# Pulsar_Buddy_SM.net
KiCad netlist of a schematic drawn in EAGLE
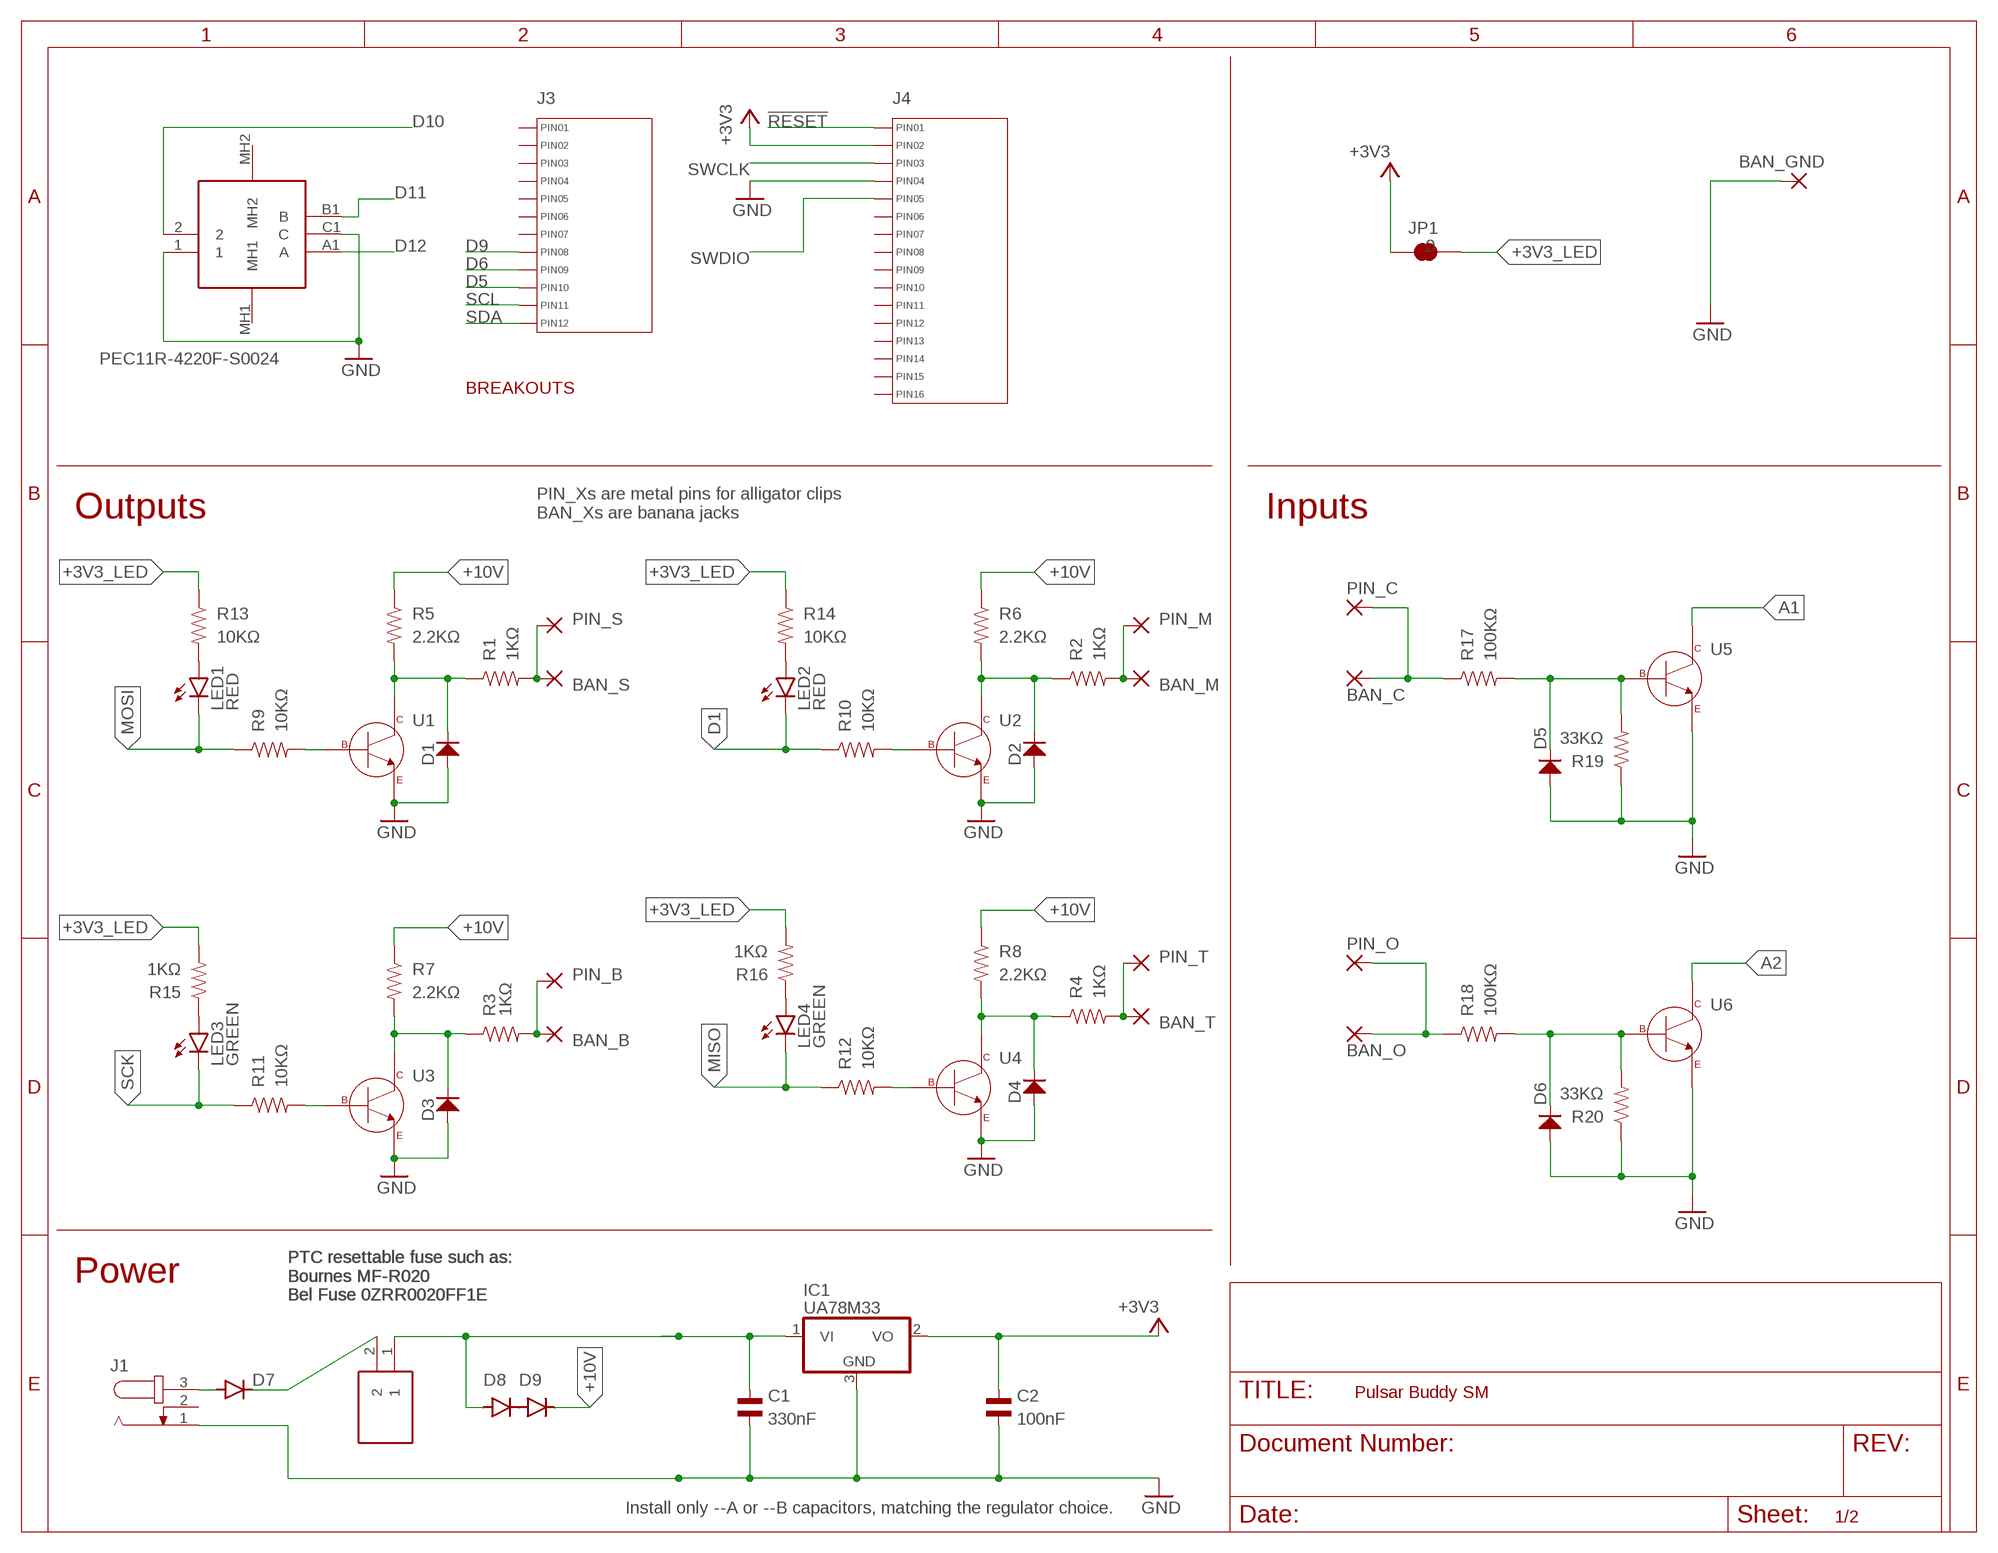
[diagram p0: schematic, sheet 1]
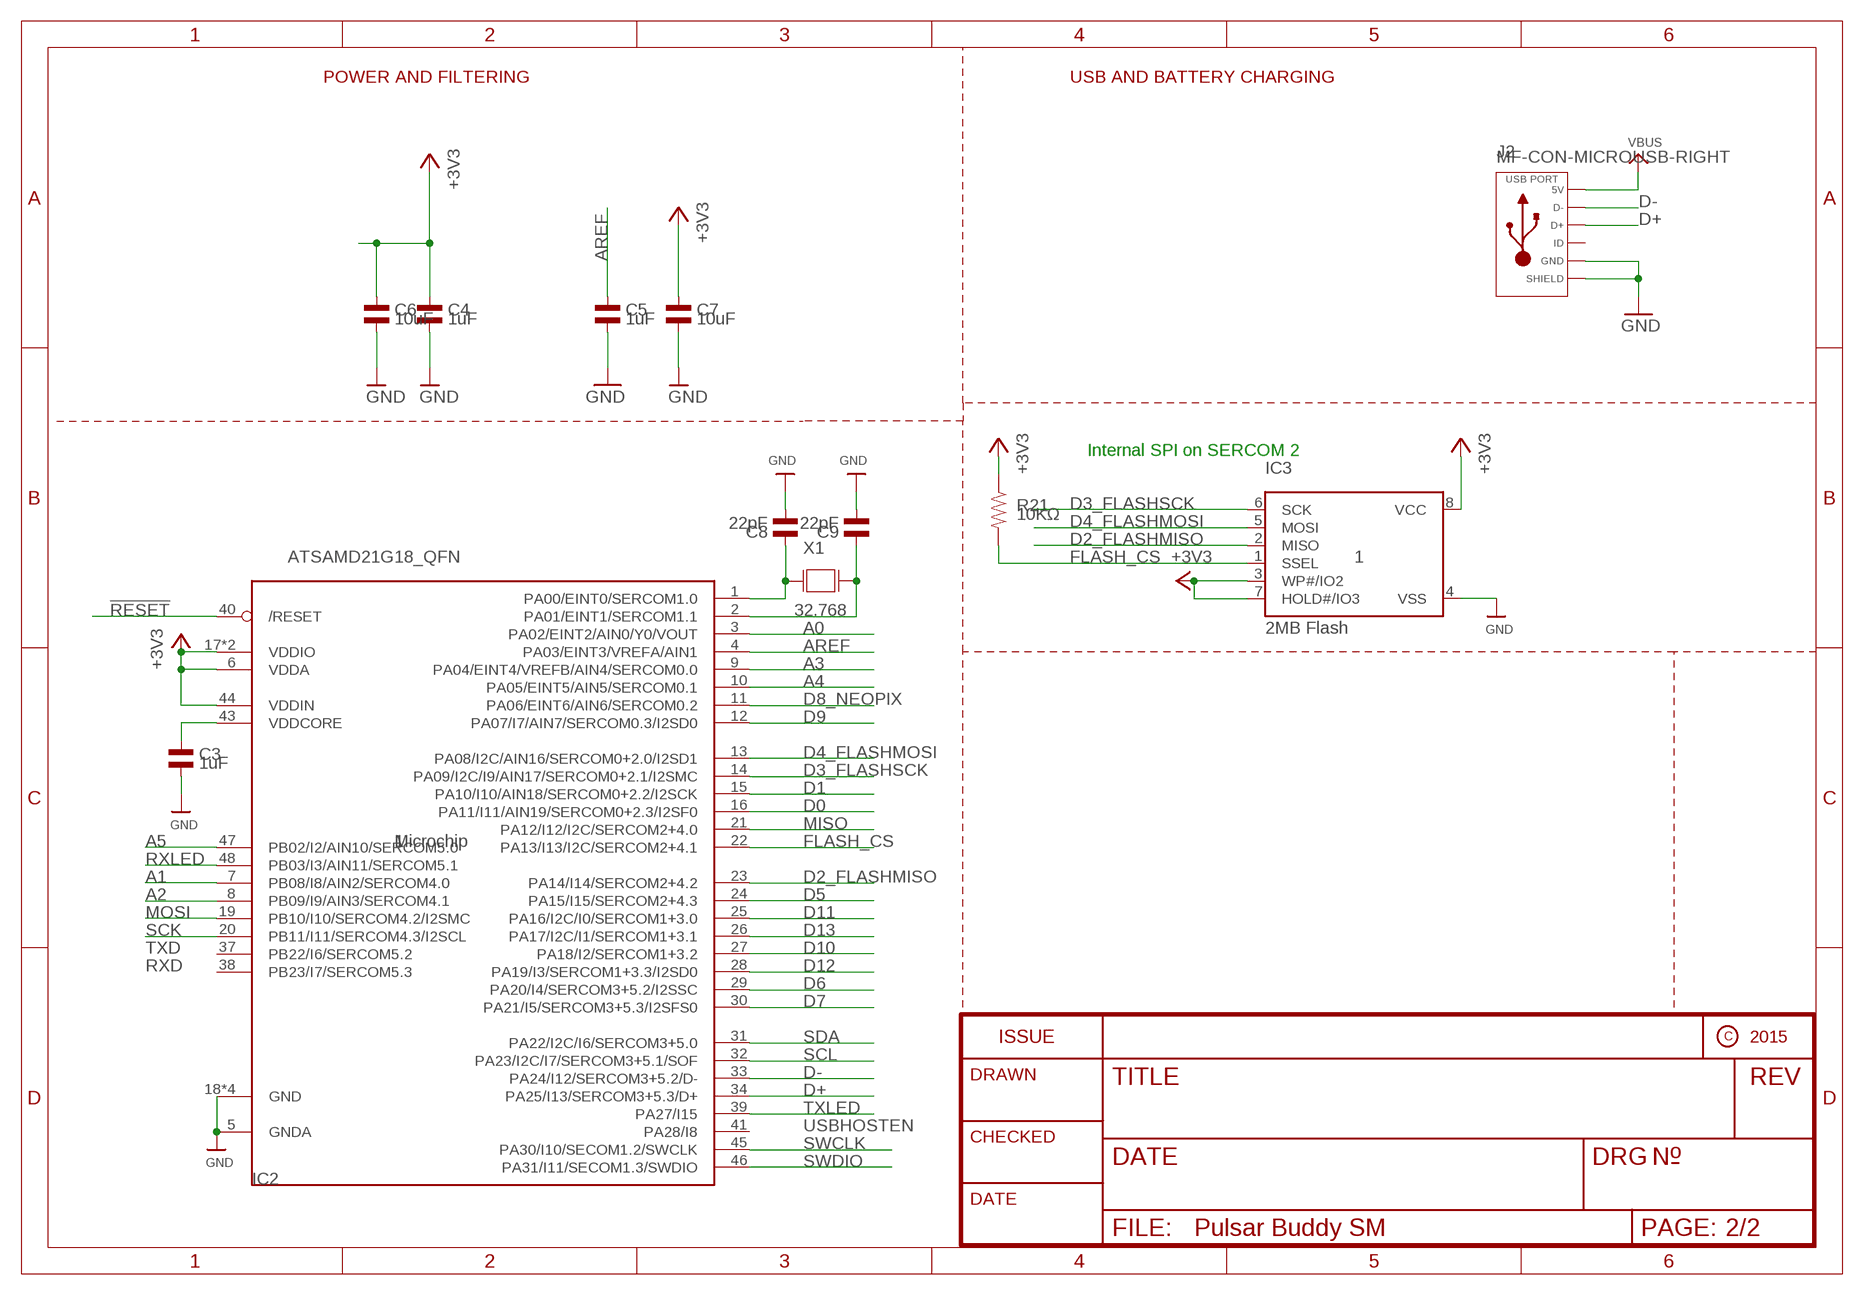
[diagram p1: schematic, sheet 2]

(export (version "E")
  (design (tool "Eeschema 10.0.6"))
  (components
    (comp (ref "C3")
      (value "1uF")
      (footprint "eagle-import:C0603")
      (fields (field (name "HOUSEPART") "YES") (field (name "MPN") "MF-CAP-0603-1uF"))
      (libsource (lib "eagle-import") (part "CAPACITOR_NP_0603"))
    )
    (comp (ref "C4")
      (value "1uF")
      (footprint "eagle-import:C0603")
      (fields (field (name "HOUSEPART") "YES") (field (name "MPN") "MF-CAP-0603-1uF"))
      (libsource (lib "eagle-import") (part "CAPACITOR_NP_0603"))
    )
    (comp (ref "C5")
      (value "1uF")
      (footprint "eagle-import:C0603")
      (fields (field (name "HOUSEPART") "YES") (field (name "MPN") "MF-CAP-0603-1uF"))
      (libsource (lib "eagle-import") (part "CAPACITOR_NP_0603"))
    )
    (comp (ref "C6")
      (value "10uF")
      (footprint "eagle-import:C0603")
      (fields (field (name "MFR") "AVX") (field (name "MPN") "0603ZD106KAT2A"))
      (libsource (lib "eagle-import") (part "CAPACITOR_NP_0603"))
    )
    (comp (ref "C7")
      (value "10uF")
      (footprint "eagle-import:C0603")
      (fields (field (name "MFR") "AVX") (field (name "MPN") "0603ZD106KAT2A"))
      (libsource (lib "eagle-import") (part "CAPACITOR_NP_0603"))
    )
    (comp (ref "C8")
      (value "22pF")
      (footprint "eagle-import:C0603")
      (fields (field (name "HOUSEPART") "YES") (field (name "MPN") "MF-CAP-0603-22pF"))
      (libsource (lib "eagle-import") (part "CAPACITOR_NP_0603"))
    )
    (comp (ref "C9")
      (value "22pF")
      (footprint "eagle-import:C0603")
      (fields (field (name "HOUSEPART") "YES") (field (name "MPN") "MF-CAP-0603-22pF"))
      (libsource (lib "eagle-import") (part "CAPACITOR_NP_0603"))
    )
    (comp (ref "IC2")
      (value "ATSAMD21G18_QFN")
      (footprint "eagle-import:TQFN48_7MM")
      (fields
        (field (name "MFR") "Microchip")
        (field (name "MPN") "SAMD21G18A-MU")
        (field (name "POPULATE") "1")
      )
      (libsource (lib "eagle-import") (part "ATSAMD21G_QFN"))
    )
    (comp (ref "IC3")
      (value "2MB Flash")
      (footprint "eagle-import:SOIC8_208MIL")
      (fields
        (field (name "MFR") "Cypress")
        (field (name "MPN") "S25FL064LABMFI010")
        (field (name "POPULATE") "1")
      )
      (libsource (lib "eagle-import") (part "SPIFLASH_SOIC8208MIL"))
    )
    (comp (ref "J2")
      (value "MF-CON-MICROUSB-RIGHT")
      (footprint "eagle-import:MICROUSB-RIGHT")
      (fields (field (name "HOUSEPART") "YES"))
      (libsource (lib "eagle-import") (part "USB_MICRO_RIGHT"))
    )
    (comp (ref "R21")
      (value "10KΩ")
      (footprint "eagle-import:R0603")
      (fields (field (name "MPN") "MF-RES-0603-10K"))
      (libsource (lib "eagle-import") (part "RESISTOR_0603"))
    )
    (comp (ref "U$34")
      (value "FIDUCIAL_100MIL")
      (footprint "eagle-import:FIDUCIAL_100MIL")
      (fields (field (name "HOUSEPART") "NO"))
      (libsource (lib "eagle-import") (part "FIDUCIAL_100MIL"))
    )
    (comp (ref "U$35")
      (value "FIDUCIAL_100MIL")
      (footprint "eagle-import:FIDUCIAL_100MIL")
      (fields (field (name "HOUSEPART") "NO"))
      (libsource (lib "eagle-import") (part "FIDUCIAL_100MIL"))
    )
    (comp (ref "X1")
      (value "32.768")
      (footprint "eagle-import:ECX-31B_SERIES")
      (fields
        (field (name "HOUSEPART") "NO")
        (field (name "MFR") "ECS International")
        (field (name "MPN") "ECS-.327-7-12-C-TR")
      )
      (libsource (lib "eagle-import") (part "CYRSTAL_ECX-31B"))
    )
    (comp (ref "BAN_B")
      (value "WIREPADBANANA")
      (footprint "eagle-import:BANANA")
      (fields (field (name "POPULATE") "0"))
      (libsource (lib "eagle-import") (part "WIREPADBANANA"))
    )
    (comp (ref "BAN_C")
      (value "WIREPADBANANA")
      (footprint "eagle-import:BANANA")
      (fields (field (name "POPULATE") "0"))
      (libsource (lib "eagle-import") (part "WIREPADBANANA"))
    )
    (comp (ref "BAN_GND")
      (value "WIREPADBANANA-GND")
      (footprint "eagle-import:BANANA-GND")
      (fields (field (name "POPULATE") "0"))
      (libsource (lib "eagle-import") (part "WIREPADBANANA-GND"))
    )
    (comp (ref "BAN_M")
      (value "WIREPADBANANA")
      (footprint "eagle-import:BANANA")
      (fields (field (name "POPULATE") "0"))
      (libsource (lib "eagle-import") (part "WIREPADBANANA"))
    )
    (comp (ref "BAN_O")
      (value "WIREPADBANANA")
      (footprint "eagle-import:BANANA")
      (fields (field (name "POPULATE") "0"))
      (libsource (lib "eagle-import") (part "WIREPADBANANA"))
    )
    (comp (ref "BAN_S")
      (value "WIREPADBANANA")
      (footprint "eagle-import:BANANA")
      (fields (field (name "POPULATE") "0"))
      (libsource (lib "eagle-import") (part "WIREPADBANANA"))
    )
    (comp (ref "BAN_T")
      (value "WIREPADBANANA")
      (footprint "eagle-import:BANANA")
      (fields (field (name "POPULATE") "0"))
      (libsource (lib "eagle-import") (part "WIREPADBANANA"))
    )
    (comp (ref "C1")
      (value "330nF")
      (footprint "eagle-import:C0603")
      (fields (field (name "MFR") "Yageo") (field (name "MPN") "CC0603ZRY5V7BB334"))
      (libsource (lib "eagle-import") (part "CAPACITOR_NP_0603"))
    )
    (comp (ref "C2")
      (value "100nF")
      (footprint "eagle-import:C0603")
      (fields (field (name "MFR") "Yageo") (field (name "MPN") "CC0603KRX7R9BB104"))
      (libsource (lib "eagle-import") (part "CAPACITOR_NP_0603"))
    )
    (comp (ref "D1")
      (value "MF-DIO-SOD123-BAT42")
      (footprint "eagle-import:SOD-123")
      (fields (field (name "HOUSEPART") "YES"))
      (libsource (lib "eagle-import") (part "DIODES_SOD-123_BAT42"))
    )
    (comp (ref "D2")
      (value "MF-DIO-SOD123-BAT42")
      (footprint "eagle-import:SOD-123")
      (fields (field (name "HOUSEPART") "YES"))
      (libsource (lib "eagle-import") (part "DIODES_SOD-123_BAT42"))
    )
    (comp (ref "D3")
      (value "MF-DIO-SOD123-BAT42")
      (footprint "eagle-import:SOD-123")
      (fields (field (name "HOUSEPART") "YES"))
      (libsource (lib "eagle-import") (part "DIODES_SOD-123_BAT42"))
    )
    (comp (ref "D4")
      (value "MF-DIO-SOD123-BAT42")
      (footprint "eagle-import:SOD-123")
      (fields (field (name "HOUSEPART") "YES"))
      (libsource (lib "eagle-import") (part "DIODES_SOD-123_BAT42"))
    )
    (comp (ref "D5")
      (value "MF-DIO-SOD123-BAT42")
      (footprint "eagle-import:SOD-123")
      (fields (field (name "HOUSEPART") "YES"))
      (libsource (lib "eagle-import") (part "DIODES_SOD-123_BAT42"))
    )
    (comp (ref "D6")
      (value "MF-DIO-SOD123-BAT42")
      (footprint "eagle-import:SOD-123")
      (fields (field (name "HOUSEPART") "YES"))
      (libsource (lib "eagle-import") (part "DIODES_SOD-123_BAT42"))
    )
    (comp (ref "D7")
      (value "CGRM4004-G")
      (footprint "eagle-import:SOD-123_MINI-SMA")
      (fields (field (name "MFR") "Comchip") (field (name "MPN") "CGRM4004-G") (field (name "POPULATE") "1"))
      (libsource (lib "eagle-import") (part "CGRM400-G4"))
    )
    (comp (ref "D8")
      (value "CGRM4004-G")
      (footprint "eagle-import:SOD-123_MINI-SMA")
      (fields (field (name "MFR") "Comchip") (field (name "MPN") "CGRM4004-G") (field (name "POPULATE") "1"))
      (libsource (lib "eagle-import") (part "CGRM400-G4"))
    )
    (comp (ref "D9")
      (value "CGRM4004-G")
      (footprint "eagle-import:SOD-123_MINI-SMA")
      (fields (field (name "MFR") "Comchip") (field (name "MPN") "CGRM4004-G") (field (name "POPULATE") "1"))
      (libsource (lib "eagle-import") (part "CGRM400-G4"))
    )
    (comp (ref "F1")
      (value "0ZCJ0020FF2E")
      (footprint "eagle-import:FUSC3216X75N")
      (fields (field (name "MFR") "Bel Fuse") (field (name "MPN") "0ZCJ0020FF2E"))
      (libsource (lib "eagle-import") (part "0ZCJ0020FF2E"))
    )
    (comp (ref "IC1")
      (value "UA78M33")
      (footprint "eagle-import:TO252")
      (fields
        (field (name "MFR") "Texas Instruments")
        (field (name "MPN") "UA78M33CKVURG3")
        (field (name "POPULATE") "1")
      )
      (libsource (lib "eagle-import") (part "78DT05"))
    )
    (comp (ref "J1")
      (value "JACK-PLUG0")
      (footprint "eagle-import:SPC4077")
      (fields (field (name "POPULATE") "0"))
      (libsource (lib "eagle-import") (part "JACK-PLUG0"))
    )
    (comp (ref "J3")
      (value "MF-CON-2.54mm-01x12")
      (footprint "eagle-import:PTH_2.54MM_01X12")
      (fields (field (name "HOUSEPART") "YES"))
      (libsource (lib "eagle-import") (part "CON_01X12_PTH_2.54MM"))
    )
    (comp (ref "J4")
      (value "MF-CON-2.54mm-01x16")
      (footprint "eagle-import:PTH_2.54MM_01X16")
      (fields (field (name "HOUSEPART") "YES"))
      (libsource (lib "eagle-import") (part "CON_01X16_PTH_2.54MM"))
    )
    (comp (ref "JP1")
      (value "JUMPER-SMT_2_NC_TRACE_SILK")
      (footprint "eagle-import:SMT-JUMPER_2_NC_TRACE_SILK")
      (fields (field (name "POPULATE") "0"))
      (libsource (lib "eagle-import") (part "JUMPER-SMT_2_NC_TRACE_SILK"))
    )
    (comp (ref "LED1")
      (value "RED")
      (footprint "eagle-import:LED5MM")
      (libsource (lib "eagle-import") (part "LED5MM"))
    )
    (comp (ref "LED2")
      (value "RED")
      (footprint "eagle-import:LED5MM")
      (libsource (lib "eagle-import") (part "LED5MM"))
    )
    (comp (ref "LED3")
      (value "GREEN")
      (footprint "eagle-import:LED5MM")
      (libsource (lib "eagle-import") (part "LED5MM"))
    )
    (comp (ref "LED4")
      (value "GREEN")
      (footprint "eagle-import:LED5MM")
      (libsource (lib "eagle-import") (part "LED5MM"))
    )
    (comp (ref "PIN_B")
      (value "WIREPAD")
      (footprint "eagle-import:M3")
      (fields (field (name "POPULATE") "0"))
      (libsource (lib "eagle-import") (part "WIREPAD"))
    )
    (comp (ref "PIN_C")
      (value "WIREPAD")
      (footprint "eagle-import:M3")
      (fields (field (name "POPULATE") "0"))
      (libsource (lib "eagle-import") (part "WIREPAD"))
    )
    (comp (ref "PIN_M")
      (value "WIREPAD")
      (footprint "eagle-import:M3")
      (fields (field (name "POPULATE") "0"))
      (libsource (lib "eagle-import") (part "WIREPAD"))
    )
    (comp (ref "PIN_O")
      (value "WIREPAD")
      (footprint "eagle-import:M3")
      (fields (field (name "POPULATE") "0"))
      (libsource (lib "eagle-import") (part "WIREPAD"))
    )
    (comp (ref "PIN_S")
      (value "WIREPAD")
      (footprint "eagle-import:M3")
      (fields (field (name "POPULATE") "0"))
      (libsource (lib "eagle-import") (part "WIREPAD"))
    )
    (comp (ref "PIN_T")
      (value "WIREPAD")
      (footprint "eagle-import:M3")
      (fields (field (name "POPULATE") "0"))
      (libsource (lib "eagle-import") (part "WIREPAD"))
    )
    (comp (ref "R1")
      (value "1KΩ")
      (footprint "eagle-import:R0603")
      (fields (field (name "MPN") "MF-RES-0603-1K"))
      (libsource (lib "eagle-import") (part "RESISTOR_0603"))
    )
    (comp (ref "R2")
      (value "1KΩ")
      (footprint "eagle-import:R0603")
      (fields (field (name "MPN") "MF-RES-0603-1K"))
      (libsource (lib "eagle-import") (part "RESISTOR_0603"))
    )
    (comp (ref "R3")
      (value "1KΩ")
      (footprint "eagle-import:R0603")
      (fields (field (name "MPN") "MF-RES-0603-1K"))
      (libsource (lib "eagle-import") (part "RESISTOR_0603"))
    )
    (comp (ref "R4")
      (value "1KΩ")
      (footprint "eagle-import:R0603")
      (fields (field (name "MPN") "MF-RES-0603-1K"))
      (libsource (lib "eagle-import") (part "RESISTOR_0603"))
    )
    (comp (ref "R5")
      (value "2.2KΩ")
      (footprint "eagle-import:R0603")
      (fields (field (name "MFR") "Yageo") (field (name "MPN") "RC0603JR-072K2L"))
      (libsource (lib "eagle-import") (part "RESISTOR_0603"))
    )
    (comp (ref "R6")
      (value "2.2KΩ")
      (footprint "eagle-import:R0603")
      (fields (field (name "MFR") "Yageo") (field (name "MPN") "RC0603JR-072K2L"))
      (libsource (lib "eagle-import") (part "RESISTOR_0603"))
    )
    (comp (ref "R7")
      (value "2.2KΩ")
      (footprint "eagle-import:R0603")
      (fields (field (name "MFR") "Yageo") (field (name "MPN") "RC0603JR-072K2L"))
      (libsource (lib "eagle-import") (part "RESISTOR_0603"))
    )
    (comp (ref "R8")
      (value "2.2KΩ")
      (footprint "eagle-import:R0603")
      (fields (field (name "MFR") "Yageo") (field (name "MPN") "RC0603JR-072K2L"))
      (libsource (lib "eagle-import") (part "RESISTOR_0603"))
    )
    (comp (ref "R9")
      (value "10KΩ")
      (footprint "eagle-import:R0603")
      (fields (field (name "MPN") "MF-RES-0603-10K"))
      (libsource (lib "eagle-import") (part "RESISTOR_0603"))
    )
    (comp (ref "R10")
      (value "10KΩ")
      (footprint "eagle-import:R0603")
      (fields (field (name "MPN") "MF-RES-0603-10K"))
      (libsource (lib "eagle-import") (part "RESISTOR_0603"))
    )
    (comp (ref "R11")
      (value "10KΩ")
      (footprint "eagle-import:R0603")
      (fields (field (name "MPN") "MF-RES-0603-10K"))
      (libsource (lib "eagle-import") (part "RESISTOR_0603"))
    )
    (comp (ref "R12")
      (value "10KΩ")
      (footprint "eagle-import:R0603")
      (fields (field (name "MPN") "MF-RES-0603-10K"))
      (libsource (lib "eagle-import") (part "RESISTOR_0603"))
    )
    (comp (ref "R13")
      (value "10KΩ")
      (footprint "eagle-import:R0603")
      (fields (field (name "MPN") "MF-RES-0603-10K"))
      (libsource (lib "eagle-import") (part "RESISTOR_0603"))
    )
    (comp (ref "R14")
      (value "10KΩ")
      (footprint "eagle-import:R0603")
      (fields (field (name "MPN") "MF-RES-0603-10K"))
      (libsource (lib "eagle-import") (part "RESISTOR_0603"))
    )
    (comp (ref "R15")
      (value "1KΩ")
      (footprint "eagle-import:R0603")
      (fields (field (name "MPN") "MF-RES-0603-1K"))
      (libsource (lib "eagle-import") (part "RESISTOR_0603"))
    )
    (comp (ref "R16")
      (value "1KΩ")
      (footprint "eagle-import:R0603")
      (fields (field (name "MPN") "MF-RES-0603-1K"))
      (libsource (lib "eagle-import") (part "RESISTOR_0603"))
    )
    (comp (ref "R17")
      (value "100KΩ")
      (footprint "eagle-import:R0603")
      (fields (field (name "MPN") "MF-RES-0603-100K"))
      (libsource (lib "eagle-import") (part "RESISTOR_0603"))
    )
    (comp (ref "R18")
      (value "100KΩ")
      (footprint "eagle-import:R0603")
      (fields (field (name "MPN") "MF-RES-0603-100K"))
      (libsource (lib "eagle-import") (part "RESISTOR_0603"))
    )
    (comp (ref "R19")
      (value "33KΩ")
      (footprint "eagle-import:R0603")
      (fields (field (name "MFR") "Yageo") (field (name "MPN") "RC0603FR-0733KL"))
      (libsource (lib "eagle-import") (part "RESISTOR_0603"))
    )
    (comp (ref "R20")
      (value "33KΩ")
      (footprint "eagle-import:R0603")
      (fields (field (name "MFR") "Yageo") (field (name "MPN") "RC0603FR-0733KL"))
      (libsource (lib "eagle-import") (part "RESISTOR_0603"))
    )
    (comp (ref "SW1")
      (value "PEC11R-4220F-S0024")
      (footprint "eagle-import:PEC11R4220FS0024")
      (fields
        (field (name "MOUSER_PART_NUMBER") "652-PEC11R-4220F-S24")
        (field (name "RS_PART_NUMBER") "7377767P")
        (field (name "MFR") "Bourns")
        (field (name "MPN") "PEC11R-4220F-S0024")
      )
      (libsource (lib "eagle-import") (part "PEC11R-4220F-S0024"))
    )
    (comp (ref "U1")
      (value "MF-DSC-SOT233-MMBT3904")
      (footprint "eagle-import:SOT-23-3")
      (fields (field (name "HOUSEPART") "YES"))
      (libsource (lib "eagle-import") (part "NPN_BJT_SOT-23-3MMBT3904"))
    )
    (comp (ref "U2")
      (value "MF-DSC-SOT233-MMBT3904")
      (footprint "eagle-import:SOT-23-3")
      (fields (field (name "HOUSEPART") "YES"))
      (libsource (lib "eagle-import") (part "NPN_BJT_SOT-23-3MMBT3904"))
    )
    (comp (ref "U3")
      (value "MF-DSC-SOT233-MMBT3904")
      (footprint "eagle-import:SOT-23-3")
      (fields (field (name "HOUSEPART") "YES"))
      (libsource (lib "eagle-import") (part "NPN_BJT_SOT-23-3MMBT3904"))
    )
    (comp (ref "U4")
      (value "MF-DSC-SOT233-MMBT3904")
      (footprint "eagle-import:SOT-23-3")
      (fields (field (name "HOUSEPART") "YES"))
      (libsource (lib "eagle-import") (part "NPN_BJT_SOT-23-3MMBT3904"))
    )
    (comp (ref "U5")
      (value "MF-DSC-SOT233-MMBT3904")
      (footprint "eagle-import:SOT-23-3")
      (fields (field (name "HOUSEPART") "YES"))
      (libsource (lib "eagle-import") (part "NPN_BJT_SOT-23-3MMBT3904"))
    )
    (comp (ref "U6")
      (value "MF-DSC-SOT233-MMBT3904")
      (footprint "eagle-import:SOT-23-3")
      (fields (field (name "HOUSEPART") "YES"))
      (libsource (lib "eagle-import") (part "NPN_BJT_SOT-23-3MMBT3904"))
    )
  )
  (nets
    (net (code "1") (name "+3V3") (class "Default")
      (node (ref "C2") (pin "P$1") (pinfunction "P$1_P$1") (pintype "passive"))
      (node (ref "C4") (pin "P$1") (pinfunction "P$1_P$1") (pintype "passive"))
      (node (ref "C6") (pin "P$1") (pinfunction "P$1_P$1") (pintype "passive"))
      (node (ref "C7") (pin "P$1") (pinfunction "P$1_P$1") (pintype "passive"))
      (node (ref "IC1") (pin "2") (pinfunction "VO_2") (pintype "passive"))
      (node (ref "IC2") (pin "17") (pinfunction "VDDIO_17") (pintype "power_in"))
      (node (ref "IC2") (pin "36") (pinfunction "VDDIO_36") (pintype "power_in"))
      (node (ref "IC2") (pin "44") (pinfunction "VDDIN_44") (pintype "power_in"))
      (node (ref "IC2") (pin "6") (pinfunction "VDDA_6") (pintype "power_in"))
      (node (ref "IC3") (pin "3") (pinfunction "WP#/IO2_3") (pintype "bidirectional"))
      (node (ref "IC3") (pin "7") (pinfunction "HOLD#/IO3_7") (pintype "bidirectional"))
      (node (ref "IC3") (pin "8") (pinfunction "VCC_8") (pintype "bidirectional"))
      (node (ref "J4") (pin "P$2") (pinfunction "PIN2_P$2") (pintype "bidirectional"))
      (node (ref "JP1") (pin "1") (pinfunction "1_1") (pintype "passive"))
      (node (ref "R21") (pin "P$1") (pinfunction "P$1_P$1") (pintype "passive"))
    )
    (net (code "2") (name "+3V3_LED") (class "Default")
      (node (ref "JP1") (pin "2") (pinfunction "2_2") (pintype "passive"))
      (node (ref "R13") (pin "P$1") (pinfunction "P$1_P$1") (pintype "passive"))
      (node (ref "R14") (pin "P$1") (pinfunction "P$1_P$1") (pintype "passive"))
      (node (ref "R15") (pin "P$2") (pinfunction "P$2_P$2") (pintype "passive"))
      (node (ref "R16") (pin "P$2") (pinfunction "P$2_P$2") (pintype "passive"))
    )
    (net (code "3") (name "+10V") (class "Default")
      (node (ref "D9") (pin "C") (pinfunction "C_C") (pintype "passive"))
      (node (ref "R5") (pin "P$1") (pinfunction "P$1_P$1") (pintype "passive"))
      (node (ref "R6") (pin "P$1") (pinfunction "P$1_P$1") (pintype "passive"))
      (node (ref "R7") (pin "P$1") (pinfunction "P$1_P$1") (pintype "passive"))
      (node (ref "R8") (pin "P$1") (pinfunction "P$1_P$1") (pintype "passive"))
    )
    (net (code "4") (name "A0") (class "Default")
      (node (ref "IC2") (pin "3") (pinfunction "PA02/EINT2/AIN0/Y0/VOUT_3") (pintype "bidirectional"))
    )
    (net (code "5") (name "A1") (class "Default")
      (node (ref "IC2") (pin "7") (pinfunction "PB08/I8/AIN2/SERCOM4.0_7") (pintype "bidirectional"))
      (node (ref "U5") (pin "P$3") (pinfunction "COLLECTOR_P$3") (pintype "bidirectional"))
    )
    (net (code "6") (name "A2") (class "Default")
      (node (ref "IC2") (pin "8") (pinfunction "PB09/I9/AIN3/SERCOM4.1_8") (pintype "bidirectional"))
      (node (ref "U6") (pin "P$3") (pinfunction "COLLECTOR_P$3") (pintype "bidirectional"))
    )
    (net (code "7") (name "A3") (class "Default")
      (node (ref "IC2") (pin "9") (pinfunction "PA04/EINT4/VREFB/AIN4/SERCOM0.0_9") (pintype "bidirectional"))
    )
    (net (code "8") (name "A4") (class "Default")
      (node (ref "IC2") (pin "10") (pinfunction "PA05/EINT5/AIN5/SERCOM0.1_10") (pintype "bidirectional"))
    )
    (net (code "9") (name "A5") (class "Default")
      (node (ref "IC2") (pin "47") (pinfunction "PB02/I2/AIN10/SERCOM5.0_47") (pintype "bidirectional"))
    )
    (net (code "10") (name "AREF") (class "Default")
      (node (ref "C5") (pin "P$1") (pinfunction "P$1_P$1") (pintype "passive"))
      (node (ref "IC2") (pin "4") (pinfunction "PA03/EINT3/VREFA/AIN1_4") (pintype "bidirectional"))
    )
    (net (code "11") (name "D+") (class "Default")
      (node (ref "IC2") (pin "34") (pinfunction "PA25/I13/SERCOM3+5.3/D+_34") (pintype "bidirectional"))
      (node (ref "J2") (pin "3") (pinfunction "D+_3") (pintype "bidirectional"))
    )
    (net (code "12") (name "D-") (class "Default")
      (node (ref "IC2") (pin "33") (pinfunction "PA24/I12/SERCOM3+5.2/D-_33") (pintype "bidirectional"))
      (node (ref "J2") (pin "2") (pinfunction "D-_2") (pintype "bidirectional"))
    )
    (net (code "13") (name "D0") (class "Default")
      (node (ref "IC2") (pin "16") (pinfunction "PA11/I11/AIN19/SERCOM0+2.3/I2SF0_16") (pintype "bidirectional"))
    )
    (net (code "14") (name "D1") (class "Default")
      (node (ref "IC2") (pin "15") (pinfunction "PA10/I10/AIN18/SERCOM0+2.2/I2SCK_15") (pintype "bidirectional"))
      (node (ref "LED2") (pin "K") (pinfunction "C_K") (pintype "passive"))
      (node (ref "R10") (pin "P$1") (pinfunction "P$1_P$1") (pintype "passive"))
    )
    (net (code "15") (name "D2_FLASHMISO") (class "Default")
      (node (ref "IC2") (pin "23") (pinfunction "PA14/I14/SERCOM2+4.2_23") (pintype "bidirectional"))
      (node (ref "IC3") (pin "2") (pinfunction "MISO_2") (pintype "bidirectional"))
    )
    (net (code "16") (name "D3_FLASHSCK") (class "Default")
      (node (ref "IC2") (pin "14") (pinfunction "PA09/I2C/I9/AIN17/SERCOM0+2.1/I2SMC_14") (pintype "bidirectional"))
      (node (ref "IC3") (pin "6") (pinfunction "SCK_6") (pintype "bidirectional"))
    )
    (net (code "17") (name "D4_FLASHMOSI") (class "Default")
      (node (ref "IC2") (pin "13") (pinfunction "PA08/I2C/AIN16/SERCOM0+2.0/I2SD1_13") (pintype "bidirectional"))
      (node (ref "IC3") (pin "5") (pinfunction "MOSI_5") (pintype "bidirectional"))
    )
    (net (code "18") (name "D5") (class "Default")
      (node (ref "IC2") (pin "24") (pinfunction "PA15/I15/SERCOM2+4.3_24") (pintype "bidirectional"))
      (node (ref "J3") (pin "P$10") (pinfunction "PIN10_P$10") (pintype "bidirectional"))
    )
    (net (code "19") (name "D6") (class "Default")
      (node (ref "IC2") (pin "29") (pinfunction "PA20/I4/SERCOM3+5.2/I2SSC_29") (pintype "bidirectional"))
      (node (ref "J3") (pin "P$9") (pinfunction "PIN9_P$9") (pintype "bidirectional"))
    )
    (net (code "20") (name "D7") (class "Default")
      (node (ref "IC2") (pin "30") (pinfunction "PA21/I5/SERCOM3+5.3/I2SFS0_30") (pintype "bidirectional"))
    )
    (net (code "21") (name "D8_NEOPIX") (class "Default")
      (node (ref "IC2") (pin "11") (pinfunction "PA06/EINT6/AIN6/SERCOM0.2_11") (pintype "bidirectional"))
    )
    (net (code "22") (name "D9") (class "Default")
      (node (ref "IC2") (pin "12") (pinfunction "PA07/I7/AIN7/SERCOM0.3/I2SD0_12") (pintype "bidirectional"))
      (node (ref "J3") (pin "P$8") (pinfunction "PIN8_P$8") (pintype "bidirectional"))
    )
    (net (code "23") (name "D10") (class "Default")
      (node (ref "IC2") (pin "27") (pinfunction "PA18/I2/SERCOM1+3.2_27") (pintype "bidirectional"))
      (node (ref "SW1") (pin "2") (pinfunction "2_2") (pintype "bidirectional"))
    )
    (net (code "24") (name "D11") (class "Default")
      (node (ref "IC2") (pin "25") (pinfunction "PA16/I2C/I0/SERCOM1+3.0_25") (pintype "bidirectional"))
      (node (ref "SW1") (pin "B1") (pinfunction "B_B1") (pintype "bidirectional"))
    )
    (net (code "25") (name "D12") (class "Default")
      (node (ref "IC2") (pin "28") (pinfunction "PA19/I3/SERCOM1+3.3/I2SD0_28") (pintype "bidirectional"))
      (node (ref "SW1") (pin "A1") (pinfunction "A_A1") (pintype "bidirectional"))
    )
    (net (code "26") (name "D13") (class "Default")
      (node (ref "IC2") (pin "26") (pinfunction "PA17/I2C/I1/SERCOM1+3.1_26") (pintype "bidirectional"))
    )
    (net (code "27") (name "FLASH_CS") (class "Default")
      (node (ref "IC2") (pin "22") (pinfunction "PA13/I13/I2C/SERCOM2+4.1_22") (pintype "bidirectional"))
      (node (ref "IC3") (pin "1") (pinfunction "SSEL_1") (pintype "bidirectional"))
      (node (ref "R21") (pin "P$2") (pinfunction "P$2_P$2") (pintype "passive"))
    )
    (net (code "28") (name "GND") (class "Default")
      (node (ref "BAN_GND") (pin "C") (pinfunction "P_C") (pintype "passive"))
      (node (ref "C1") (pin "P$2") (pinfunction "P$2_P$2") (pintype "passive"))
      (node (ref "C2") (pin "P$2") (pinfunction "P$2_P$2") (pintype "passive"))
      (node (ref "C3") (pin "P$2") (pinfunction "P$2_P$2") (pintype "passive"))
      (node (ref "C4") (pin "P$2") (pinfunction "P$2_P$2") (pintype "passive"))
      (node (ref "C5") (pin "P$2") (pinfunction "P$2_P$2") (pintype "passive"))
      (node (ref "C6") (pin "P$2") (pinfunction "P$2_P$2") (pintype "passive"))
      (node (ref "C7") (pin "P$2") (pinfunction "P$2_P$2") (pintype "passive"))
      (node (ref "C8") (pin "P$2") (pinfunction "P$2_P$2") (pintype "passive"))
      (node (ref "C9") (pin "P$2") (pinfunction "P$2_P$2") (pintype "passive"))
      (node (ref "D1") (pin "ANODE") (pinfunction "ANODE_ANODE") (pintype "bidirectional"))
      (node (ref "D2") (pin "ANODE") (pinfunction "ANODE_ANODE") (pintype "bidirectional"))
      (node (ref "D3") (pin "ANODE") (pinfunction "ANODE_ANODE") (pintype "bidirectional"))
      (node (ref "D4") (pin "ANODE") (pinfunction "ANODE_ANODE") (pintype "bidirectional"))
      (node (ref "D5") (pin "ANODE") (pinfunction "ANODE_ANODE") (pintype "bidirectional"))
      (node (ref "D6") (pin "ANODE") (pinfunction "ANODE_ANODE") (pintype "bidirectional"))
      (node (ref "IC1") (pin "3") (pinfunction "GND_3") (pintype "passive"))
      (node (ref "IC2") (pin "18") (pinfunction "GND_18") (pintype "power_in"))
      (node (ref "IC2") (pin "35") (pinfunction "GND_35") (pintype "power_in"))
      (node (ref "IC2") (pin "42") (pinfunction "GND_42") (pintype "power_in"))
      (node (ref "IC2") (pin "5") (pinfunction "GNDA_5") (pintype "power_in"))
      (node (ref "IC2") (pin "THERMAL") (pinfunction "GND_THERMAL") (pintype "power_in"))
      (node (ref "IC3") (pin "4") (pinfunction "VSS_4") (pintype "bidirectional"))
      (node (ref "J1") (pin "1") (pinfunction "1_1") (pintype "passive"))
      (node (ref "J2") (pin "5") (pinfunction "GND_5") (pintype "power_in"))
      (node (ref "J2") (pin "S1") (pinfunction "SLD_S1") (pintype "power_in"))
      (node (ref "J2") (pin "S2") (pinfunction "SLD_S2") (pintype "power_in"))
      (node (ref "J2") (pin "S3") (pinfunction "SLD_S3") (pintype "power_in"))
      (node (ref "J2") (pin "S4") (pinfunction "SLD_S4") (pintype "power_in"))
      (node (ref "J2") (pin "S5") (pinfunction "SLD_S5") (pintype "power_in"))
      (node (ref "J2") (pin "S6") (pinfunction "SLD_S6") (pintype "power_in"))
      (node (ref "J4") (pin "P$4") (pinfunction "PIN4_P$4") (pintype "bidirectional"))
      (node (ref "R19") (pin "P$1") (pinfunction "P$1_P$1") (pintype "passive"))
      (node (ref "R20") (pin "P$1") (pinfunction "P$1_P$1") (pintype "passive"))
      (node (ref "SW1") (pin "1") (pinfunction "1_1") (pintype "bidirectional"))
      (node (ref "SW1") (pin "C1") (pinfunction "C_C1") (pintype "bidirectional"))
      (node (ref "U1") (pin "P$2") (pinfunction "EMITTER_P$2") (pintype "bidirectional"))
      (node (ref "U2") (pin "P$2") (pinfunction "EMITTER_P$2") (pintype "bidirectional"))
      (node (ref "U3") (pin "P$2") (pinfunction "EMITTER_P$2") (pintype "bidirectional"))
      (node (ref "U4") (pin "P$2") (pinfunction "EMITTER_P$2") (pintype "bidirectional"))
      (node (ref "U5") (pin "P$2") (pinfunction "EMITTER_P$2") (pintype "bidirectional"))
      (node (ref "U6") (pin "P$2") (pinfunction "EMITTER_P$2") (pintype "bidirectional"))
    )
    (net (code "29") (name "MISO") (class "Default")
      (node (ref "IC2") (pin "21") (pinfunction "PA12/I12/I2C/SERCOM2+4.0_21") (pintype "bidirectional"))
      (node (ref "LED4") (pin "K") (pinfunction "C_K") (pintype "passive"))
      (node (ref "R12") (pin "P$1") (pinfunction "P$1_P$1") (pintype "passive"))
    )
    (net (code "30") (name "MOSI") (class "Default")
      (node (ref "IC2") (pin "19") (pinfunction "PB10/I10/SERCOM4.2/I2SMC_19") (pintype "bidirectional"))
      (node (ref "LED1") (pin "K") (pinfunction "C_K") (pintype "passive"))
      (node (ref "R9") (pin "P$1") (pinfunction "P$1_P$1") (pintype "passive"))
    )
    (net (code "31") (name "Net-(BAN_B-P)") (class "Default")
      (node (ref "BAN_B") (pin "C") (pinfunction "P_C") (pintype "passive"))
      (node (ref "PIN_B") (pin "1") (pinfunction "P_1") (pintype "passive"))
      (node (ref "R3") (pin "P$2") (pinfunction "P$2_P$2") (pintype "passive"))
    )
    (net (code "32") (name "Net-(BAN_C-P)") (class "Default")
      (node (ref "BAN_C") (pin "C") (pinfunction "P_C") (pintype "passive"))
      (node (ref "PIN_C") (pin "1") (pinfunction "P_1") (pintype "passive"))
      (node (ref "R17") (pin "P$1") (pinfunction "P$1_P$1") (pintype "passive"))
    )
    (net (code "33") (name "Net-(BAN_M-P)") (class "Default")
      (node (ref "BAN_M") (pin "C") (pinfunction "P_C") (pintype "passive"))
      (node (ref "PIN_M") (pin "1") (pinfunction "P_1") (pintype "passive"))
      (node (ref "R2") (pin "P$2") (pinfunction "P$2_P$2") (pintype "passive"))
    )
    (net (code "34") (name "Net-(BAN_O-P)") (class "Default")
      (node (ref "BAN_O") (pin "C") (pinfunction "P_C") (pintype "passive"))
      (node (ref "PIN_O") (pin "1") (pinfunction "P_1") (pintype "passive"))
      (node (ref "R18") (pin "P$1") (pinfunction "P$1_P$1") (pintype "passive"))
    )
    (net (code "35") (name "Net-(BAN_S-P)") (class "Default")
      (node (ref "BAN_S") (pin "C") (pinfunction "P_C") (pintype "passive"))
      (node (ref "PIN_S") (pin "1") (pinfunction "P_1") (pintype "passive"))
      (node (ref "R1") (pin "P$2") (pinfunction "P$2_P$2") (pintype "passive"))
    )
    (net (code "36") (name "Net-(BAN_T-P)") (class "Default")
      (node (ref "BAN_T") (pin "C") (pinfunction "P_C") (pintype "passive"))
      (node (ref "PIN_T") (pin "1") (pinfunction "P_1") (pintype "passive"))
      (node (ref "R4") (pin "P$2") (pinfunction "P$2_P$2") (pintype "passive"))
    )
    (net (code "37") (name "Net-(D7-PadA)") (class "Default")
      (node (ref "D7") (pin "A") (pinfunction "A_A") (pintype "passive"))
      (node (ref "J1") (pin "3") (pinfunction "3_3") (pintype "passive"))
    )
    (net (code "38") (name "Net-(D7-PadC)") (class "Default")
      (node (ref "D7") (pin "C") (pinfunction "C_C") (pintype "passive"))
      (node (ref "F1") (pin "2") (pinfunction "2_2") (pintype "bidirectional"))
    )
    (net (code "39") (name "Net-(D8-PadC)") (class "Default")
      (node (ref "D8") (pin "C") (pinfunction "C_C") (pintype "passive"))
      (node (ref "D9") (pin "A") (pinfunction "A_A") (pintype "passive"))
    )
    (net (code "40") (name "Net-(IC1-VI)") (class "Default")
      (node (ref "C1") (pin "P$1") (pinfunction "P$1_P$1") (pintype "passive"))
      (node (ref "D8") (pin "A") (pinfunction "A_A") (pintype "passive"))
      (node (ref "F1") (pin "1") (pinfunction "1_1") (pintype "bidirectional"))
      (node (ref "IC1") (pin "1") (pinfunction "VI_1") (pintype "input"))
    )
    (net (code "41") (name "Net-(IC2-PA00{slash}EINT0{slash}SERCOM1.0)") (class "Default")
      (node (ref "C8") (pin "P$1") (pinfunction "P$1_P$1") (pintype "passive"))
      (node (ref "IC2") (pin "1") (pinfunction "PA00/EINT0/SERCOM1.0_1") (pintype "bidirectional"))
      (node (ref "X1") (pin "P$1") (pinfunction "X0_P$1") (pintype "bidirectional"))
    )
    (net (code "42") (name "Net-(IC2-PA01{slash}EINT1{slash}SERCOM1.1)") (class "Default")
      (node (ref "C9") (pin "P$1") (pinfunction "P$1_P$1") (pintype "passive"))
      (node (ref "IC2") (pin "2") (pinfunction "PA01/EINT1/SERCOM1.1_2") (pintype "bidirectional"))
      (node (ref "X1") (pin "P$2") (pinfunction "X1_P$2") (pintype "bidirectional"))
    )
    (net (code "43") (name "Net-(IC2-VDDCORE)") (class "Default")
      (node (ref "C3") (pin "P$1") (pinfunction "P$1_P$1") (pintype "passive"))
      (node (ref "IC2") (pin "43") (pinfunction "VDDCORE_43") (pintype "power_in"))
    )
    (net (code "44") (name "Net-(LED1-PadA)") (class "Default")
      (node (ref "LED1") (pin "A") (pinfunction "A_A") (pintype "passive"))
      (node (ref "R13") (pin "P$2") (pinfunction "P$2_P$2") (pintype "passive"))
    )
    (net (code "45") (name "Net-(LED2-PadA)") (class "Default")
      (node (ref "LED2") (pin "A") (pinfunction "A_A") (pintype "passive"))
      (node (ref "R14") (pin "P$2") (pinfunction "P$2_P$2") (pintype "passive"))
    )
    (net (code "46") (name "Net-(LED3-PadA)") (class "Default")
      (node (ref "LED3") (pin "A") (pinfunction "A_A") (pintype "passive"))
      (node (ref "R15") (pin "P$1") (pinfunction "P$1_P$1") (pintype "passive"))
    )
    (net (code "47") (name "Net-(LED4-PadA)") (class "Default")
      (node (ref "LED4") (pin "A") (pinfunction "A_A") (pintype "passive"))
      (node (ref "R16") (pin "P$1") (pinfunction "P$1_P$1") (pintype "passive"))
    )
    (net (code "48") (name "Net-(U1-BASE)") (class "Default")
      (node (ref "R9") (pin "P$2") (pinfunction "P$2_P$2") (pintype "passive"))
      (node (ref "U1") (pin "P$1") (pinfunction "BASE_P$1") (pintype "bidirectional"))
    )
    (net (code "49") (name "Net-(U1-COLLECTOR)") (class "Default")
      (node (ref "D1") (pin "CATHODE") (pinfunction "CATHODE_CATHODE") (pintype "bidirectional"))
      (node (ref "R1") (pin "P$1") (pinfunction "P$1_P$1") (pintype "passive"))
      (node (ref "R5") (pin "P$2") (pinfunction "P$2_P$2") (pintype "passive"))
      (node (ref "U1") (pin "P$3") (pinfunction "COLLECTOR_P$3") (pintype "bidirectional"))
    )
    (net (code "50") (name "Net-(U2-BASE)") (class "Default")
      (node (ref "R10") (pin "P$2") (pinfunction "P$2_P$2") (pintype "passive"))
      (node (ref "U2") (pin "P$1") (pinfunction "BASE_P$1") (pintype "bidirectional"))
    )
    (net (code "51") (name "Net-(U2-COLLECTOR)") (class "Default")
      (node (ref "D2") (pin "CATHODE") (pinfunction "CATHODE_CATHODE") (pintype "bidirectional"))
      (node (ref "R2") (pin "P$1") (pinfunction "P$1_P$1") (pintype "passive"))
      (node (ref "R6") (pin "P$2") (pinfunction "P$2_P$2") (pintype "passive"))
      (node (ref "U2") (pin "P$3") (pinfunction "COLLECTOR_P$3") (pintype "bidirectional"))
    )
    (net (code "52") (name "Net-(U3-BASE)") (class "Default")
      (node (ref "R11") (pin "P$2") (pinfunction "P$2_P$2") (pintype "passive"))
      (node (ref "U3") (pin "P$1") (pinfunction "BASE_P$1") (pintype "bidirectional"))
    )
    (net (code "53") (name "Net-(U3-COLLECTOR)") (class "Default")
      (node (ref "D3") (pin "CATHODE") (pinfunction "CATHODE_CATHODE") (pintype "bidirectional"))
      (node (ref "R3") (pin "P$1") (pinfunction "P$1_P$1") (pintype "passive"))
      (node (ref "R7") (pin "P$2") (pinfunction "P$2_P$2") (pintype "passive"))
      (node (ref "U3") (pin "P$3") (pinfunction "COLLECTOR_P$3") (pintype "bidirectional"))
    )
    (net (code "54") (name "Net-(U4-BASE)") (class "Default")
      (node (ref "R12") (pin "P$2") (pinfunction "P$2_P$2") (pintype "passive"))
      (node (ref "U4") (pin "P$1") (pinfunction "BASE_P$1") (pintype "bidirectional"))
    )
    (net (code "55") (name "Net-(U4-COLLECTOR)") (class "Default")
      (node (ref "D4") (pin "CATHODE") (pinfunction "CATHODE_CATHODE") (pintype "bidirectional"))
      (node (ref "R4") (pin "P$1") (pinfunction "P$1_P$1") (pintype "passive"))
      (node (ref "R8") (pin "P$2") (pinfunction "P$2_P$2") (pintype "passive"))
      (node (ref "U4") (pin "P$3") (pinfunction "COLLECTOR_P$3") (pintype "bidirectional"))
    )
    (net (code "56") (name "Net-(U5-BASE)") (class "Default")
      (node (ref "D5") (pin "CATHODE") (pinfunction "CATHODE_CATHODE") (pintype "bidirectional"))
      (node (ref "R17") (pin "P$2") (pinfunction "P$2_P$2") (pintype "passive"))
      (node (ref "R19") (pin "P$2") (pinfunction "P$2_P$2") (pintype "passive"))
      (node (ref "U5") (pin "P$1") (pinfunction "BASE_P$1") (pintype "bidirectional"))
    )
    (net (code "57") (name "Net-(U6-BASE)") (class "Default")
      (node (ref "D6") (pin "CATHODE") (pinfunction "CATHODE_CATHODE") (pintype "bidirectional"))
      (node (ref "R18") (pin "P$2") (pinfunction "P$2_P$2") (pintype "passive"))
      (node (ref "R20") (pin "P$2") (pinfunction "P$2_P$2") (pintype "passive"))
      (node (ref "U6") (pin "P$1") (pinfunction "BASE_P$1") (pintype "bidirectional"))
    )
    (net (code "58") (name "RXLED") (class "Default")
      (node (ref "IC2") (pin "48") (pinfunction "PB03/I3/AIN11/SERCOM5.1_48") (pintype "bidirectional"))
    )
    (net (code "59") (name "SCK") (class "Default")
      (node (ref "IC2") (pin "20") (pinfunction "PB11/I11/SERCOM4.3/I2SCL_20") (pintype "bidirectional"))
      (node (ref "LED3") (pin "K") (pinfunction "C_K") (pintype "passive"))
      (node (ref "R11") (pin "P$1") (pinfunction "P$1_P$1") (pintype "passive"))
    )
    (net (code "60") (name "SCL") (class "Default")
      (node (ref "IC2") (pin "32") (pinfunction "PA23/I2C/I7/SERCOM3+5.1/SOF_32") (pintype "bidirectional"))
      (node (ref "J3") (pin "P$11") (pinfunction "PIN11_P$11") (pintype "bidirectional"))
    )
    (net (code "61") (name "SDA") (class "Default")
      (node (ref "IC2") (pin "31") (pinfunction "PA22/I2C/I6/SERCOM3+5.0_31") (pintype "bidirectional"))
      (node (ref "J3") (pin "P$12") (pinfunction "PIN12_P$12") (pintype "bidirectional"))
    )
    (net (code "62") (name "SWCLK") (class "Default")
      (node (ref "IC2") (pin "45") (pinfunction "PA30/I10/SECOM1.2/SWCLK_45") (pintype "bidirectional"))
      (node (ref "J4") (pin "P$3") (pinfunction "PIN3_P$3") (pintype "bidirectional"))
    )
    (net (code "63") (name "SWDIO") (class "Default")
      (node (ref "IC2") (pin "46") (pinfunction "PA31/I11/SECOM1.3/SWDIO_46") (pintype "bidirectional"))
      (node (ref "J4") (pin "P$5") (pinfunction "PIN5_P$5") (pintype "bidirectional"))
    )
    (net (code "64") (name "TXLED") (class "Default")
      (node (ref "IC2") (pin "39") (pinfunction "PA27/I15_39") (pintype "bidirectional"))
    )
    (net (code "65") (name "VBUS") (class "Default")
      (node (ref "J2") (pin "1") (pinfunction "5V_1") (pintype "power_in"))
    )
    (net (code "66") (name "unconnected-(IC2-PA28{slash}I8-Pad41)") (class "Default")
      (node (ref "IC2") (pin "41") (pinfunction "PA28/I8_41") (pintype "bidirectional"))
    )
    (net (code "67") (name "unconnected-(IC2-PB22{slash}I6{slash}SERCOM5.2-Pad37)") (class "Default")
      (node (ref "IC2") (pin "37") (pinfunction "PB22/I6/SERCOM5.2_37") (pintype "bidirectional"))
    )
    (net (code "68") (name "unconnected-(IC2-PB23{slash}I7{slash}SERCOM5.3-Pad38)") (class "Default")
      (node (ref "IC2") (pin "38") (pinfunction "PB23/I7/SERCOM5.3_38") (pintype "bidirectional"))
    )
    (net (code "69") (name "unconnected-(J1-Pad2)") (class "Default")
      (node (ref "J1") (pin "2") (pinfunction "2_2") (pintype "passive"))
    )
    (net (code "70") (name "unconnected-(J2-ID-Pad4)") (class "Default")
      (node (ref "J2") (pin "4") (pinfunction "ID_4") (pintype "bidirectional"))
    )
    (net (code "71") (name "unconnected-(J3-PIN1-PadP$1)") (class "Default")
      (node (ref "J3") (pin "P$1") (pinfunction "PIN1_P$1") (pintype "bidirectional"))
    )
    (net (code "72") (name "unconnected-(J3-PIN2-PadP$2)") (class "Default")
      (node (ref "J3") (pin "P$2") (pinfunction "PIN2_P$2") (pintype "bidirectional"))
    )
    (net (code "73") (name "unconnected-(J3-PIN3-PadP$3)") (class "Default")
      (node (ref "J3") (pin "P$3") (pinfunction "PIN3_P$3") (pintype "bidirectional"))
    )
    (net (code "74") (name "unconnected-(J3-PIN4-PadP$4)") (class "Default")
      (node (ref "J3") (pin "P$4") (pinfunction "PIN4_P$4") (pintype "bidirectional"))
    )
    (net (code "75") (name "unconnected-(J3-PIN5-PadP$5)") (class "Default")
      (node (ref "J3") (pin "P$5") (pinfunction "PIN5_P$5") (pintype "bidirectional"))
    )
    (net (code "76") (name "unconnected-(J3-PIN6-PadP$6)") (class "Default")
      (node (ref "J3") (pin "P$6") (pinfunction "PIN6_P$6") (pintype "bidirectional"))
    )
    (net (code "77") (name "unconnected-(J3-PIN7-PadP$7)") (class "Default")
      (node (ref "J3") (pin "P$7") (pinfunction "PIN7_P$7") (pintype "bidirectional"))
    )
    (net (code "78") (name "unconnected-(J4-PIN6-PadP$6)") (class "Default")
      (node (ref "J4") (pin "P$6") (pinfunction "PIN6_P$6") (pintype "bidirectional"))
    )
    (net (code "79") (name "unconnected-(J4-PIN7-PadP$7)") (class "Default")
      (node (ref "J4") (pin "P$7") (pinfunction "PIN7_P$7") (pintype "bidirectional"))
    )
    (net (code "80") (name "unconnected-(J4-PIN8-PadP$8)") (class "Default")
      (node (ref "J4") (pin "P$8") (pinfunction "PIN8_P$8") (pintype "bidirectional"))
    )
    (net (code "81") (name "unconnected-(J4-PIN9-PadP$9)") (class "Default")
      (node (ref "J4") (pin "P$9") (pinfunction "PIN9_P$9") (pintype "bidirectional"))
    )
    (net (code "82") (name "unconnected-(J4-PIN10-PadP$10)") (class "Default")
      (node (ref "J4") (pin "P$10") (pinfunction "PIN10_P$10") (pintype "bidirectional"))
    )
    (net (code "83") (name "unconnected-(J4-PIN11-PadP$11)") (class "Default")
      (node (ref "J4") (pin "P$11") (pinfunction "PIN11_P$11") (pintype "bidirectional"))
    )
    (net (code "84") (name "unconnected-(J4-PIN12-PadP$12)") (class "Default")
      (node (ref "J4") (pin "P$12") (pinfunction "PIN12_P$12") (pintype "bidirectional"))
    )
    (net (code "85") (name "unconnected-(J4-PIN13-PadP$13)") (class "Default")
      (node (ref "J4") (pin "P$13") (pinfunction "PIN13_P$13") (pintype "bidirectional"))
    )
    (net (code "86") (name "unconnected-(J4-PIN14-PadP$14)") (class "Default")
      (node (ref "J4") (pin "P$14") (pinfunction "PIN14_P$14") (pintype "bidirectional"))
    )
    (net (code "87") (name "unconnected-(J4-PIN15-PadP$15)") (class "Default")
      (node (ref "J4") (pin "P$15") (pinfunction "PIN15_P$15") (pintype "bidirectional"))
    )
    (net (code "88") (name "unconnected-(J4-PIN16-PadP$16)") (class "Default")
      (node (ref "J4") (pin "P$16") (pinfunction "PIN16_P$16") (pintype "bidirectional"))
    )
    (net (code "89") (name "unconnected-(SW1-PadMH1)") (class "Default")
      (node (ref "SW1") (pin "MH1") (pinfunction "MH1_MH1") (pintype "bidirectional"))
    )
    (net (code "90") (name "unconnected-(SW1-PadMH2)") (class "Default")
      (node (ref "SW1") (pin "MH2") (pinfunction "MH2_MH2") (pintype "bidirectional"))
    )
    (net (code "91") (name "~{RESET}") (class "Default")
      (node (ref "IC2") (pin "40") (pinfunction "/RESET_40") (pintype "bidirectional"))
      (node (ref "J4") (pin "P$1") (pinfunction "PIN1_P$1") (pintype "bidirectional"))
    )
  )
)
